# BLDC-PWR-CONROLLER.net
KiCad netlist of a schematic drawn in Altium Designer
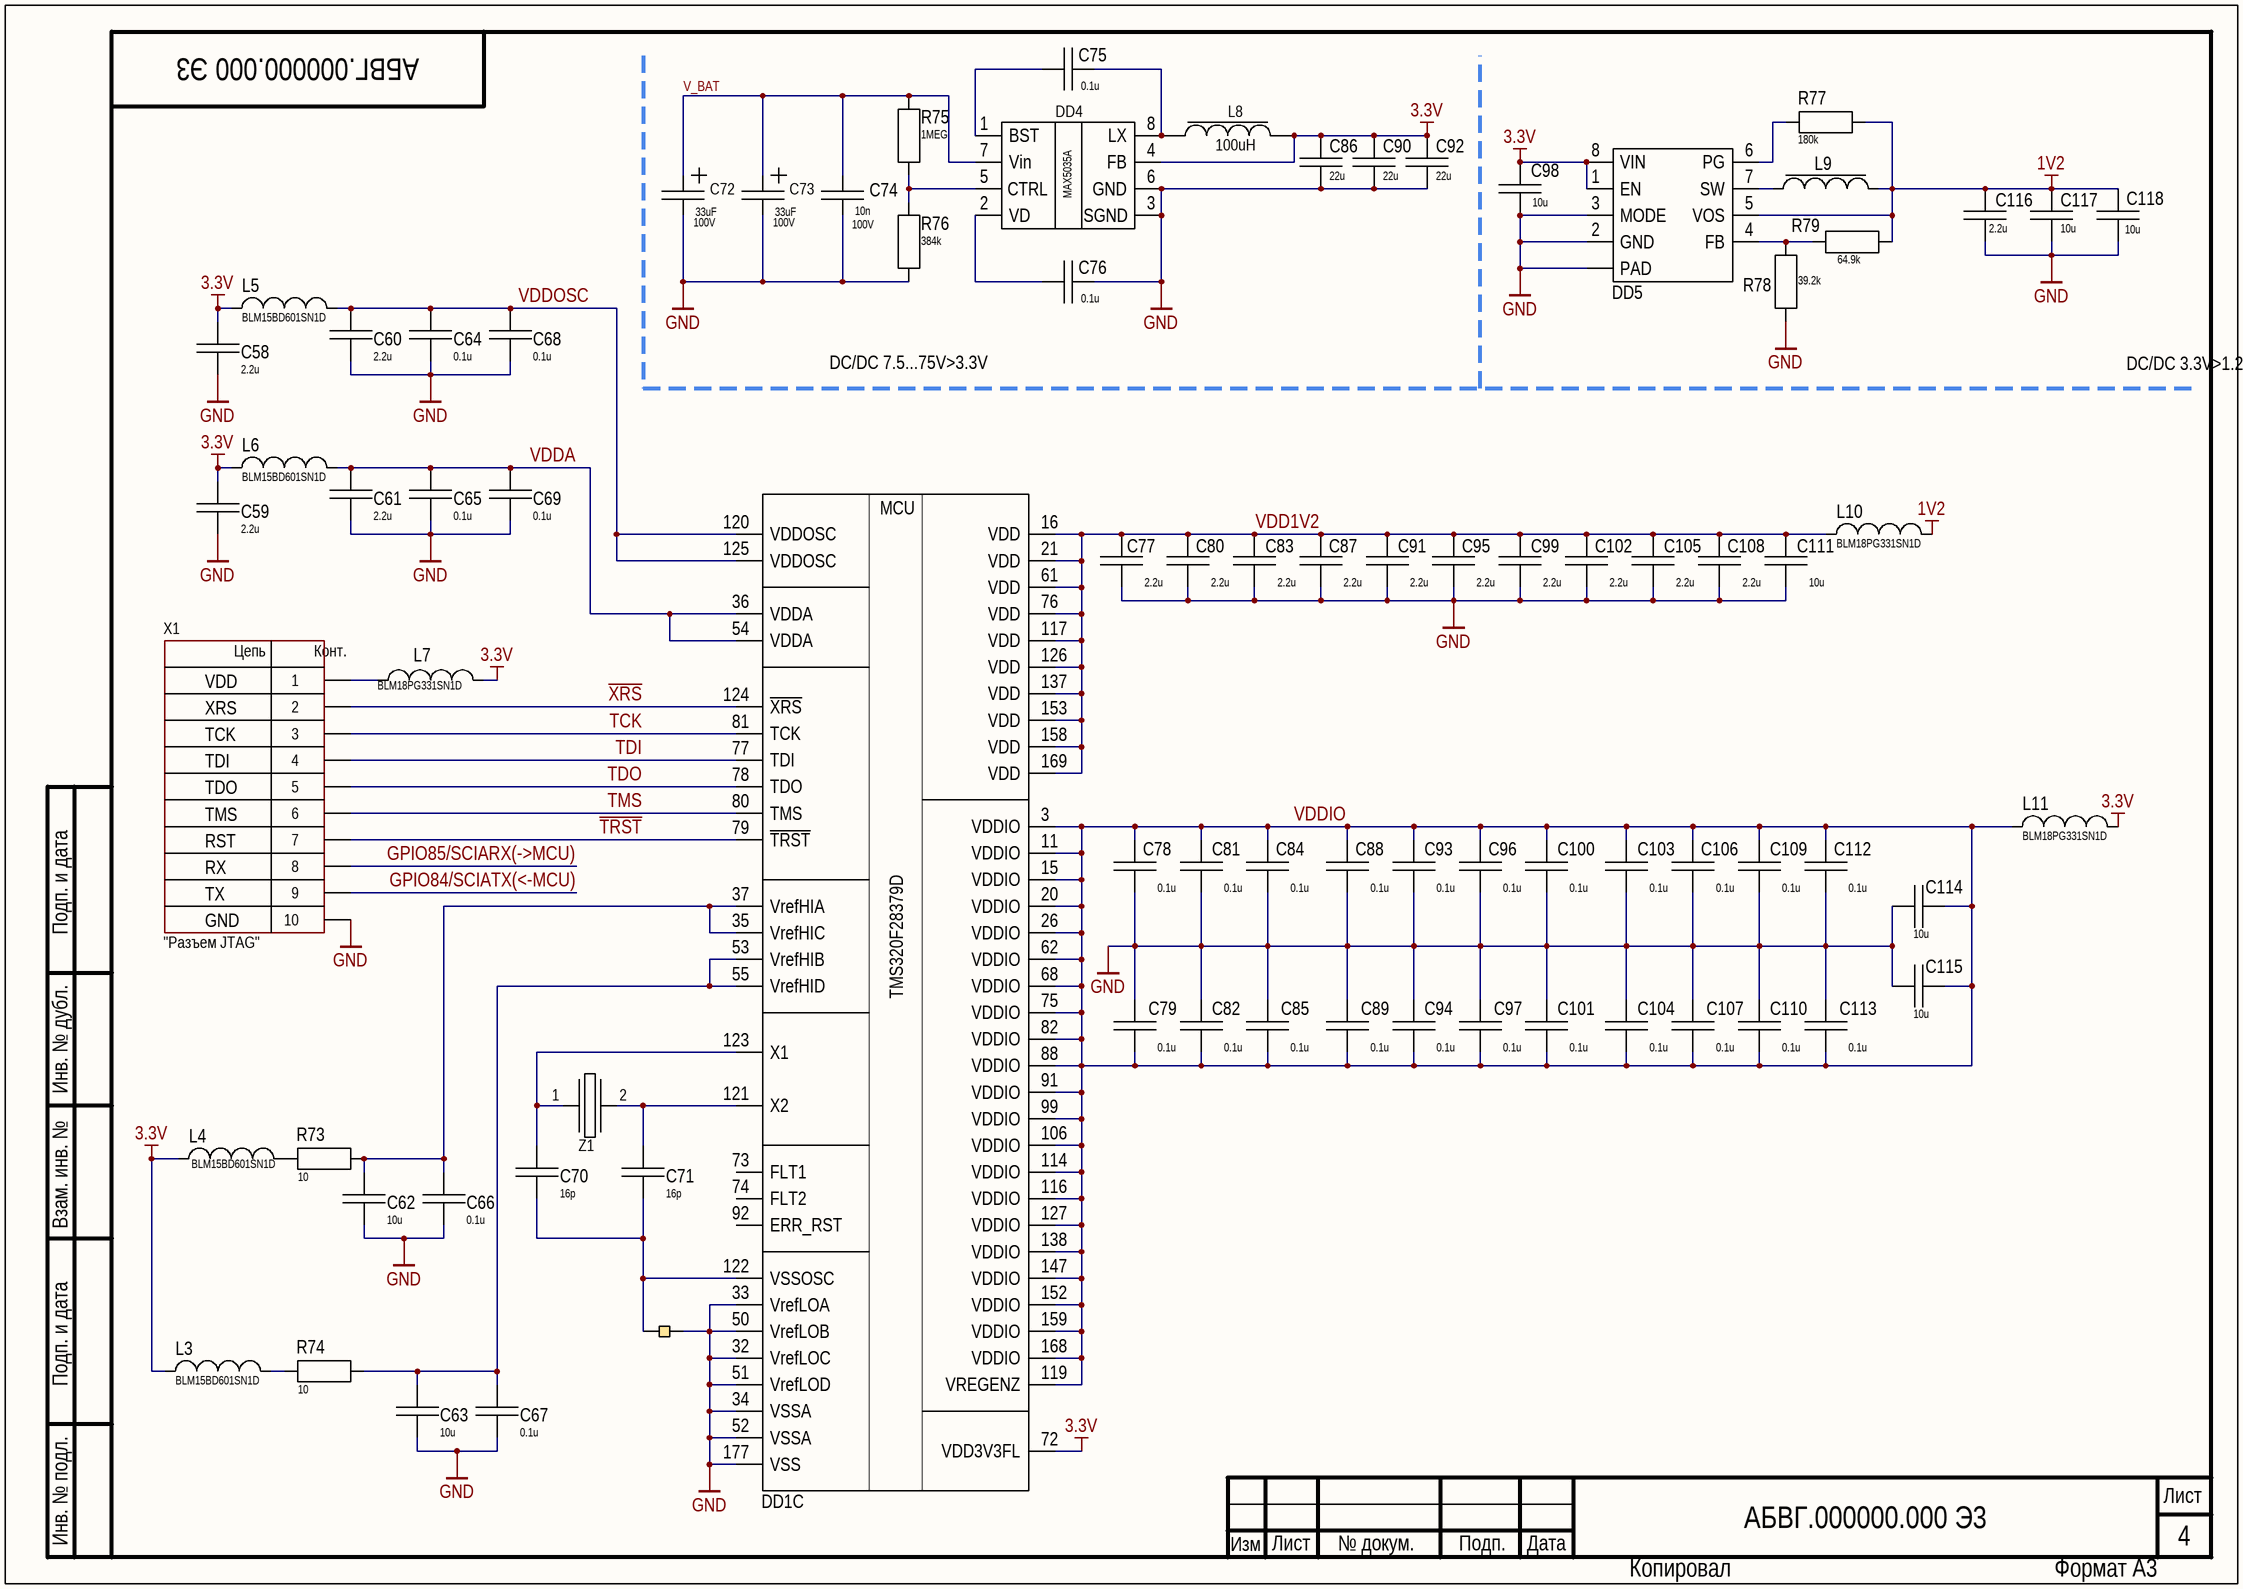
[diagram p0: BLDC-PWR-CONROLLER.SchDoc]

(export (version "E")
  (design (tool "Eeschema 10.0.6"))
  (components
    (comp (ref "C58")
      (value "2.2u")
      (footprint "CAP: 0402")
      (fields (field (name "VOLTAGE") "6.3V") (field (name "PARTNUMBER") "CC0402MRX5R5BB106"))
      (libsource (lib "Fider_Board_Lib") (part "CAP 0402"))
    )
    (comp (ref "C59")
      (value "2.2u")
      (footprint "CAP: 0402")
      (fields (field (name "VOLTAGE") "6.3V") (field (name "PARTNUMBER") "CC0402MRX5R5BB106"))
      (libsource (lib "Fider_Board_Lib") (part "CAP 0402"))
    )
    (comp (ref "C60")
      (value "2.2u")
      (footprint "CAP: 0402")
      (fields (field (name "VOLTAGE") "6.3V") (field (name "PARTNUMBER") "CC0402MRX5R5BB106"))
      (libsource (lib "Fider_Board_Lib") (part "CAP 0402"))
    )
    (comp (ref "C61")
      (value "2.2u")
      (footprint "CAP: 0402")
      (fields (field (name "VOLTAGE") "6.3V") (field (name "PARTNUMBER") "CC0402MRX5R5BB106"))
      (libsource (lib "Fider_Board_Lib") (part "CAP 0402"))
    )
    (comp (ref "C62")
      (value "10u")
      (footprint "CAP: 0402")
      (fields (field (name "VOLTAGE") "6.3V") (field (name "PARTNUMBER") "CC0402MRX5R5BB106"))
      (libsource (lib "Fider_Board_Lib") (part "CAP 0402"))
    )
    (comp (ref "C63")
      (value "10u")
      (footprint "CAP: 0402")
      (fields (field (name "VOLTAGE") "6.3V") (field (name "PARTNUMBER") "CC0402MRX5R5BB106"))
      (libsource (lib "Fider_Board_Lib") (part "CAP 0402"))
    )
    (comp (ref "C64")
      (value "0.1u")
      (footprint "CAP: 0402")
      (fields
        (field (name "VOLTAGE") "10V")
        (field (name "PARTNUMBER") "C0402C104K8PAC")
        (field (name "MANUFACTURER") "Kemet")
      )
      (libsource (lib "Fider_Board_Lib") (part "CAP 0402"))
    )
    (comp (ref "C65")
      (value "0.1u")
      (footprint "CAP: 0402")
      (fields
        (field (name "VOLTAGE") "10V")
        (field (name "PARTNUMBER") "C0402C104K8PAC")
        (field (name "MANUFACTURER") "Kemet")
      )
      (libsource (lib "Fider_Board_Lib") (part "CAP 0402"))
    )
    (comp (ref "C66")
      (value "0.1u")
      (footprint "CAP: 0402")
      (fields
        (field (name "VOLTAGE") "10V")
        (field (name "PARTNUMBER") "C0402C104K8PAC")
        (field (name "MANUFACTURER") "Kemet")
      )
      (libsource (lib "Fider_Board_Lib") (part "CAP 0402"))
    )
    (comp (ref "C67")
      (value "0.1u")
      (footprint "CAP: 0402")
      (fields
        (field (name "VOLTAGE") "10V")
        (field (name "PARTNUMBER") "C0402C104K8PAC")
        (field (name "MANUFACTURER") "Kemet")
      )
      (libsource (lib "Fider_Board_Lib") (part "CAP 0402"))
    )
    (comp (ref "C68")
      (value "0.1u")
      (footprint "CAP: 0402")
      (fields
        (field (name "VOLTAGE") "10V")
        (field (name "PARTNUMBER") "C0402C104K8PAC")
        (field (name "MANUFACTURER") "Kemet")
      )
      (libsource (lib "Fider_Board_Lib") (part "CAP 0402"))
    )
    (comp (ref "C69")
      (value "0.1u")
      (footprint "CAP: 0402")
      (fields
        (field (name "VOLTAGE") "10V")
        (field (name "PARTNUMBER") "C0402C104K8PAC")
        (field (name "MANUFACTURER") "Kemet")
      )
      (libsource (lib "Fider_Board_Lib") (part "CAP 0402"))
    )
    (comp (ref "C70")
      (value "16p")
      (footprint "CAP: 0402")
      (fields
        (field (name "VOLTAGE") "50V")
        (field (name "PARTNUMBER") "GRM1555C1H160JA01D")
        (field (name "MANUFACTURER") "Kemet")
      )
      (libsource (lib "Fider_Board_Lib") (part "CAP 0402"))
    )
    (comp (ref "C71")
      (value "16p")
      (footprint "CAP: 0402")
      (fields
        (field (name "VOLTAGE") "50V")
        (field (name "PARTNUMBER") "GRM1555C1H160JA01D")
        (field (name "MANUFACTURER") "Kemet")
      )
      (libsource (lib "Fider_Board_Lib") (part "CAP 0402"))
    )
    (comp (ref "C72")
      (value "33uF")
      (footprint "ECR08")
      (description "ECR0812")
      (fields (field (name "PARTNUMBER") "JRB2A330M03500800120000B") (field (name "VOLTAGE") "100V"))
      (libsource (lib "capacitors") (part "ECR0812"))
    )
    (comp (ref "C73")
      (value "33uF")
      (footprint "ECR08")
      (description "ECR0812")
      (fields (field (name "PARTNUMBER") "JRB2A330M03500800120000B") (field (name "VOLTAGE") "100V"))
      (libsource (lib "capacitors") (part "ECR0812"))
    )
    (comp (ref "C74")
      (value "10n")
      (footprint "StandardCase:CAP: 0603")
      (fields
        (field (name "MANUFACTURER") "murata")
        (field (name "PARTNUMBER") "GRM188R72A103KA01D")
        (field (name "VALUEMANUFACTURERPARTNUMBER") "Ceramic capacitor, 10n, X7R, ±10%, 100V, 0603, -55...+125°C")
        (field (name "VOLTAGE") "100V")
      )
      (libsource (lib "Capacitor") (part "Ceramic_0603"))
    )
    (comp (ref "C75")
      (value "0.1u")
      (footprint "CAP: 0402")
      (fields
        (field (name "VOLTAGE") "100V")
        (field (name "MANUFACTURER") "Kemet")
        (field (name "TOLERANCE") "10%")
      )
      (libsource (lib "Fider_Board_Lib") (part "CAP 0402"))
    )
    (comp (ref "C76")
      (value "0.1u")
      (footprint "CAP: 0402")
      (fields
        (field (name "VOLTAGE") "100V")
        (field (name "MANUFACTURER") "Kemet")
        (field (name "TOLERANCE") "10%")
      )
      (libsource (lib "Fider_Board_Lib") (part "CAP 0402"))
    )
    (comp (ref "C77")
      (value "2.2u")
      (footprint "CAP: 0402")
      (fields (field (name "VOLTAGE") "6.3V") (field (name "PARTNUMBER") "CC0402MRX5R5BB106"))
      (libsource (lib "Fider_Board_Lib") (part "CAP 0402"))
    )
    (comp (ref "C78")
      (value "0.1u")
      (footprint "CAP: 0402")
      (fields
        (field (name "VOLTAGE") "10V")
        (field (name "PARTNUMBER") "C0402C104K8PAC")
        (field (name "MANUFACTURER") "Kemet")
      )
      (libsource (lib "Fider_Board_Lib") (part "CAP 0402"))
    )
    (comp (ref "C79")
      (value "0.1u")
      (footprint "CAP: 0402")
      (fields
        (field (name "VOLTAGE") "10V")
        (field (name "PARTNUMBER") "C0402C104K8PAC")
        (field (name "MANUFACTURER") "Kemet")
      )
      (libsource (lib "Fider_Board_Lib") (part "CAP 0402"))
    )
    (comp (ref "C80")
      (value "2.2u")
      (footprint "CAP: 0402")
      (fields (field (name "VOLTAGE") "6.3V") (field (name "PARTNUMBER") "CC0402MRX5R5BB106"))
      (libsource (lib "Fider_Board_Lib") (part "CAP 0402"))
    )
    (comp (ref "C81")
      (value "0.1u")
      (footprint "CAP: 0402")
      (fields
        (field (name "VOLTAGE") "10V")
        (field (name "PARTNUMBER") "C0402C104K8PAC")
        (field (name "MANUFACTURER") "Kemet")
      )
      (libsource (lib "Fider_Board_Lib") (part "CAP 0402"))
    )
    (comp (ref "C82")
      (value "0.1u")
      (footprint "CAP: 0402")
      (fields
        (field (name "VOLTAGE") "10V")
        (field (name "PARTNUMBER") "C0402C104K8PAC")
        (field (name "MANUFACTURER") "Kemet")
      )
      (libsource (lib "Fider_Board_Lib") (part "CAP 0402"))
    )
    (comp (ref "C83")
      (value "2.2u")
      (footprint "CAP: 0402")
      (fields (field (name "VOLTAGE") "6.3V") (field (name "PARTNUMBER") "CC0402MRX5R5BB106"))
      (libsource (lib "Fider_Board_Lib") (part "CAP 0402"))
    )
    (comp (ref "C84")
      (value "0.1u")
      (footprint "CAP: 0402")
      (fields
        (field (name "VOLTAGE") "10V")
        (field (name "PARTNUMBER") "C0402C104K8PAC")
        (field (name "MANUFACTURER") "Kemet")
      )
      (libsource (lib "Fider_Board_Lib") (part "CAP 0402"))
    )
    (comp (ref "C85")
      (value "0.1u")
      (footprint "CAP: 0402")
      (fields
        (field (name "VOLTAGE") "10V")
        (field (name "PARTNUMBER") "C0402C104K8PAC")
        (field (name "MANUFACTURER") "Kemet")
      )
      (libsource (lib "Fider_Board_Lib") (part "CAP 0402"))
    )
    (comp (ref "C86")
      (value "22u")
      (footprint "CAP: 0805")
      (fields (field (name "VOLTAGE") "6.3V") (field (name "PARTNUMBER") "GRM21BR60J226M*"))
      (libsource (lib "Fider_Board_Lib") (part "CAP 0805"))
    )
    (comp (ref "C87")
      (value "2.2u")
      (footprint "CAP: 0402")
      (fields (field (name "VOLTAGE") "6.3V") (field (name "PARTNUMBER") "CC0402MRX5R5BB106"))
      (libsource (lib "Fider_Board_Lib") (part "CAP 0402"))
    )
    (comp (ref "C88")
      (value "0.1u")
      (footprint "CAP: 0402")
      (fields
        (field (name "VOLTAGE") "10V")
        (field (name "PARTNUMBER") "C0402C104K8PAC")
        (field (name "MANUFACTURER") "Kemet")
      )
      (libsource (lib "Fider_Board_Lib") (part "CAP 0402"))
    )
    (comp (ref "C89")
      (value "0.1u")
      (footprint "CAP: 0402")
      (fields
        (field (name "VOLTAGE") "10V")
        (field (name "PARTNUMBER") "C0402C104K8PAC")
        (field (name "MANUFACTURER") "Kemet")
      )
      (libsource (lib "Fider_Board_Lib") (part "CAP 0402"))
    )
    (comp (ref "C90")
      (value "22u")
      (footprint "CAP: 0805")
      (fields (field (name "VOLTAGE") "6.3V") (field (name "PARTNUMBER") "GRM21BR60J226M*"))
      (libsource (lib "Fider_Board_Lib") (part "CAP 0805"))
    )
    (comp (ref "C91")
      (value "2.2u")
      (footprint "CAP: 0402")
      (fields (field (name "VOLTAGE") "6.3V") (field (name "PARTNUMBER") "CC0402MRX5R5BB106"))
      (libsource (lib "Fider_Board_Lib") (part "CAP 0402"))
    )
    (comp (ref "C92")
      (value "22u")
      (footprint "CAP: 0805")
      (fields (field (name "VOLTAGE") "6.3V") (field (name "PARTNUMBER") "GRM21BR60J226M*"))
      (libsource (lib "Fider_Board_Lib") (part "CAP 0805"))
    )
    (comp (ref "C93")
      (value "0.1u")
      (footprint "CAP: 0402")
      (fields
        (field (name "VOLTAGE") "10V")
        (field (name "PARTNUMBER") "C0402C104K8PAC")
        (field (name "MANUFACTURER") "Kemet")
      )
      (libsource (lib "Fider_Board_Lib") (part "CAP 0402"))
    )
    (comp (ref "C94")
      (value "0.1u")
      (footprint "CAP: 0402")
      (fields
        (field (name "VOLTAGE") "10V")
        (field (name "PARTNUMBER") "C0402C104K8PAC")
        (field (name "MANUFACTURER") "Kemet")
      )
      (libsource (lib "Fider_Board_Lib") (part "CAP 0402"))
    )
    (comp (ref "C95")
      (value "2.2u")
      (footprint "CAP: 0402")
      (fields (field (name "VOLTAGE") "6.3V") (field (name "PARTNUMBER") "CC0402MRX5R5BB106"))
      (libsource (lib "Fider_Board_Lib") (part "CAP 0402"))
    )
    (comp (ref "C96")
      (value "0.1u")
      (footprint "CAP: 0402")
      (fields
        (field (name "VOLTAGE") "10V")
        (field (name "PARTNUMBER") "C0402C104K8PAC")
        (field (name "MANUFACTURER") "Kemet")
      )
      (libsource (lib "Fider_Board_Lib") (part "CAP 0402"))
    )
    (comp (ref "C97")
      (value "0.1u")
      (footprint "CAP: 0402")
      (fields
        (field (name "VOLTAGE") "10V")
        (field (name "PARTNUMBER") "C0402C104K8PAC")
        (field (name "MANUFACTURER") "Kemet")
      )
      (libsource (lib "Fider_Board_Lib") (part "CAP 0402"))
    )
    (comp (ref "C98")
      (value "10u")
      (footprint "CAP: 0805")
      (fields (field (name "VOLTAGE") "6.3V") (field (name "PARTNUMBER") "CC0402MRX5R5BB106"))
      (libsource (lib "Fider_Board_Lib") (part "CAP 0805"))
    )
    (comp (ref "C99")
      (value "2.2u")
      (footprint "CAP: 0402")
      (fields (field (name "VOLTAGE") "6.3V") (field (name "PARTNUMBER") "CC0402MRX5R5BB106"))
      (libsource (lib "Fider_Board_Lib") (part "CAP 0402"))
    )
    (comp (ref "C100")
      (value "0.1u")
      (footprint "CAP: 0402")
      (fields
        (field (name "VOLTAGE") "10V")
        (field (name "PARTNUMBER") "C0402C104K8PAC")
        (field (name "MANUFACTURER") "Kemet")
      )
      (libsource (lib "Fider_Board_Lib") (part "CAP 0402"))
    )
    (comp (ref "C101")
      (value "0.1u")
      (footprint "CAP: 0402")
      (fields
        (field (name "VOLTAGE") "10V")
        (field (name "PARTNUMBER") "C0402C104K8PAC")
        (field (name "MANUFACTURER") "Kemet")
      )
      (libsource (lib "Fider_Board_Lib") (part "CAP 0402"))
    )
    (comp (ref "C102")
      (value "2.2u")
      (footprint "CAP: 0402")
      (fields (field (name "VOLTAGE") "6.3V") (field (name "PARTNUMBER") "CC0402MRX5R5BB106"))
      (libsource (lib "Fider_Board_Lib") (part "CAP 0402"))
    )
    (comp (ref "C103")
      (value "0.1u")
      (footprint "CAP: 0402")
      (fields
        (field (name "VOLTAGE") "10V")
        (field (name "PARTNUMBER") "C0402C104K8PAC")
        (field (name "MANUFACTURER") "Kemet")
      )
      (libsource (lib "Fider_Board_Lib") (part "CAP 0402"))
    )
    (comp (ref "C104")
      (value "0.1u")
      (footprint "CAP: 0402")
      (fields
        (field (name "VOLTAGE") "10V")
        (field (name "PARTNUMBER") "C0402C104K8PAC")
        (field (name "MANUFACTURER") "Kemet")
      )
      (libsource (lib "Fider_Board_Lib") (part "CAP 0402"))
    )
    (comp (ref "C105")
      (value "2.2u")
      (footprint "CAP: 0402")
      (fields (field (name "VOLTAGE") "6.3V") (field (name "PARTNUMBER") "CC0402MRX5R5BB106"))
      (libsource (lib "Fider_Board_Lib") (part "CAP 0402"))
    )
    (comp (ref "C106")
      (value "0.1u")
      (footprint "CAP: 0402")
      (fields
        (field (name "VOLTAGE") "10V")
        (field (name "PARTNUMBER") "C0402C104K8PAC")
        (field (name "MANUFACTURER") "Kemet")
      )
      (libsource (lib "Fider_Board_Lib") (part "CAP 0402"))
    )
    (comp (ref "C107")
      (value "0.1u")
      (footprint "CAP: 0402")
      (fields
        (field (name "VOLTAGE") "10V")
        (field (name "PARTNUMBER") "C0402C104K8PAC")
        (field (name "MANUFACTURER") "Kemet")
      )
      (libsource (lib "Fider_Board_Lib") (part "CAP 0402"))
    )
    (comp (ref "C108")
      (value "2.2u")
      (footprint "CAP: 0402")
      (fields (field (name "VOLTAGE") "6.3V") (field (name "PARTNUMBER") "CC0402MRX5R5BB106"))
      (libsource (lib "Fider_Board_Lib") (part "CAP 0402"))
    )
    (comp (ref "C109")
      (value "0.1u")
      (footprint "CAP: 0402")
      (fields
        (field (name "VOLTAGE") "10V")
        (field (name "PARTNUMBER") "C0402C104K8PAC")
        (field (name "MANUFACTURER") "Kemet")
      )
      (libsource (lib "Fider_Board_Lib") (part "CAP 0402"))
    )
    (comp (ref "C110")
      (value "0.1u")
      (footprint "CAP: 0402")
      (fields
        (field (name "VOLTAGE") "10V")
        (field (name "PARTNUMBER") "C0402C104K8PAC")
        (field (name "MANUFACTURER") "Kemet")
      )
      (libsource (lib "Fider_Board_Lib") (part "CAP 0402"))
    )
    (comp (ref "C111")
      (value "10u")
      (footprint "CAP: 0402")
      (fields (field (name "VOLTAGE") "6.3V") (field (name "PARTNUMBER") "CC0402MRX5R5BB106"))
      (libsource (lib "Fider_Board_Lib") (part "CAP 0402"))
    )
    (comp (ref "C112")
      (value "0.1u")
      (footprint "CAP: 0402")
      (fields
        (field (name "VOLTAGE") "10V")
        (field (name "PARTNUMBER") "C0402C104K8PAC")
        (field (name "MANUFACTURER") "Kemet")
      )
      (libsource (lib "Fider_Board_Lib") (part "CAP 0402"))
    )
    (comp (ref "C113")
      (value "0.1u")
      (footprint "CAP: 0402")
      (fields
        (field (name "VOLTAGE") "10V")
        (field (name "PARTNUMBER") "C0402C104K8PAC")
        (field (name "MANUFACTURER") "Kemet")
      )
      (libsource (lib "Fider_Board_Lib") (part "CAP 0402"))
    )
    (comp (ref "C114")
      (value "10u")
      (footprint "CAP: 0402")
      (fields (field (name "VOLTAGE") "6.3V") (field (name "PARTNUMBER") "CC0402MRX5R5BB106"))
      (libsource (lib "Fider_Board_Lib") (part "CAP 0402"))
    )
    (comp (ref "C115")
      (value "10u")
      (footprint "CAP: 0402")
      (fields (field (name "VOLTAGE") "6.3V") (field (name "PARTNUMBER") "CC0402MRX5R5BB106"))
      (libsource (lib "Fider_Board_Lib") (part "CAP 0402"))
    )
    (comp (ref "C116")
      (value "2.2u")
      (footprint "CAP: 0402")
      (fields (field (name "VOLTAGE") "6.3V") (field (name "PARTNUMBER") "CC0402MRX5R5BB106"))
      (libsource (lib "Fider_Board_Lib") (part "CAP 0402"))
    )
    (comp (ref "C117")
      (value "10u")
      (footprint "CAP: 0805")
      (fields (field (name "VOLTAGE") "6.3V") (field (name "PARTNUMBER") "CC0402MRX5R5BB106"))
      (libsource (lib "Fider_Board_Lib") (part "CAP 0805"))
    )
    (comp (ref "C118")
      (value "10u")
      (footprint "CAP: 0805")
      (fields (field (name "VOLTAGE") "6.3V") (field (name "PARTNUMBER") "CC0402MRX5R5BB106"))
      (libsource (lib "Fider_Board_Lib") (part "CAP 0805"))
    )
    (comp (ref "DD1")
      (value "TMS320F28379DPTP_LACID")
      (footprint "176-HLQFP")
      (fields (field (name "PARTNUMBER") "TMS320F28379DPTPT"))
      (libsource (lib "BKM_SCH_Lib") (part "TMS320F28379DPTP_LACID"))
    )
    (comp (ref "DD4")
      (value "MAX5035A")
      (footprint "SOIC-8-150-1.27")
      (libsource (lib "BKM_SCH_Lib") (part "MAX5035*"))
    )
    (comp (ref "DD5")
      (value "TPS62080ADSGT")
      (footprint "8-WSON 2.1x2.1")
      (fields (field (name "PARTNUMBER") "TPS61023DRLR"))
      (libsource (lib "BKM_SCH_Lib") (part "TPS62080ADSGT"))
    )
    (comp (ref "L3")
      (value "BLM15BD601SN1D")
      (footprint "IND: 0402")
      (libsource (lib "Fider_Board_Lib") (part "BLM15BD601SN1D"))
    )
    (comp (ref "L4")
      (value "BLM15BD601SN1D")
      (footprint "IND: 0402")
      (libsource (lib "Fider_Board_Lib") (part "BLM15BD601SN1D"))
    )
    (comp (ref "L5")
      (value "BLM15BD601SN1D")
      (footprint "IND: 0402")
      (libsource (lib "Fider_Board_Lib") (part "BLM15BD601SN1D"))
    )
    (comp (ref "L6")
      (value "BLM15BD601SN1D")
      (footprint "IND: 0402")
      (libsource (lib "Fider_Board_Lib") (part "BLM15BD601SN1D"))
    )
    (comp (ref "L7")
      (value "BLM18PG331SN1D")
      (footprint "IND: 0603")
      (libsource (lib "") (part "BLM18PG331SN1D_1"))
    )
    (comp (ref "L8")
      (value "100uH")
      (footprint "CustomCase:IND: SRR1208")
      (fields
        (field (name "MANUFACTURER") "EPCOS")
        (field (name "PARTNUMBER") "B82477G4104M000")
        (field (name "TOLERANCE") "20%")
      )
      (libsource (lib "Inductor") (part "Inductor_SRR1208"))
    )
    (comp (ref "L9")
      (value "LQH3NPN")
      (footprint "IND: LQH3NP")
      (fields (field (name "PARTNUMBER") "LQH3NPN1R0NJ0L"))
      (libsource (lib "BKM_SCH_Lib") (part "LQH3NPN"))
    )
    (comp (ref "L10")
      (value "BLM18PG331SN1D")
      (footprint "IND: 0603")
      (libsource (lib "Fider_Board_Lib") (part "BLM18PG331SN1D"))
    )
    (comp (ref "L11")
      (value "BLM18PG331SN1D")
      (footprint "IND: 0603")
      (libsource (lib "Fider_Board_Lib") (part "BLM18PG331SN1D"))
    )
    (comp (ref "NT19") (value "~") (footprint "CON: NT") (libsource (lib "BKM_SCH_Lib") (part "NT")))
    (comp (ref "R73")
      (value "10")
      (footprint "RES: 0402")
      (fields (field (name "PARTNUMBER") "RC0402FR-071KL") (field (name "TOLERANCE") "1%"))
      (libsource (lib "Fider_Board_Lib") (part "RES 0402"))
    )
    (comp (ref "R74")
      (value "10")
      (footprint "RES: 0402")
      (fields (field (name "PARTNUMBER") "RC0402FR-071KL") (field (name "TOLERANCE") "1%"))
      (libsource (lib "Fider_Board_Lib") (part "RES 0402"))
    )
    (comp (ref "R75")
      (value "1MEG")
      (footprint "RES: 0402")
      (fields (field (name "PARTNUMBER") "RC0402FR-1339K2L") (field (name "TOLERANCE") "1%"))
      (libsource (lib "Fider_Board_Lib") (part "RES 0402"))
    )
    (comp (ref "R76")
      (value "384k")
      (footprint "RES: 0402")
      (fields (field (name "PARTNUMBER") "RC0402FR-1339K2L") (field (name "TOLERANCE") "1%"))
      (libsource (lib "Fider_Board_Lib") (part "RES 0402"))
    )
    (comp (ref "R77")
      (value "180k")
      (footprint "RES: 0402")
      (fields (field (name "PARTNUMBER") "RC0402FR-07180RL") (field (name "TOLERANCE") "1%"))
      (libsource (lib "Fider_Board_Lib") (part "RES 0402"))
    )
    (comp (ref "R78")
      (value "39.2k")
      (footprint "RES: 0402")
      (fields (field (name "PARTNUMBER") "RC0402FR-1339K2L") (field (name "TOLERANCE") "1%"))
      (libsource (lib "Fider_Board_Lib") (part "RES 0402"))
    )
    (comp (ref "R79")
      (value "64.9k")
      (footprint "RES: 0402")
      (fields (field (name "PARTNUMBER") "RC0402FR-1364K9L") (field (name "TOLERANCE") "1%"))
      (libsource (lib "Fider_Board_Lib") (part "RES 0402"))
    )
    (comp (ref "X1")
      (value "~")
      (footprint "CustomCase:CON: PLD-10")
      (fields
        (field (name "MANUFACTURER") "Connfly")
        (field (name "VALUEMANUFACTURERPARTNUMBER") "Connector, 10pin, 2.54mm, 500VAC, 3A")
        (field (name "PARTNUMBER") "PLD-10")
        (field (name "COMMENTTEXT") "\"Разъем JTAG\"")
      )
      (libsource (lib "Connector") (part "PLD-10"))
    )
    (comp (ref "Z1")
      (value "~")
      (footprint "CustomCase:OSC: HC49SM")
      (fields
        (field (name "MANUFACTURER") "Epson")
        (field (name "PARTNUMBER") "FC-135 32.7680KA-A5")
        (field (name "VALUEMANUFACTURERPARTNUMBER") "Crystal, , 12.5pF, ±20ppm, case 3215, -40...+85°C")
      )
      (libsource (lib "Oscilator") (part "Crystal_HC-49SM"))
    )
  )
  (nets
    (net (code "1") (name "/GPIO84{slash}SCIATX(<-MCU)") (class "Default")
      (node (ref "X1") (pin "9") (pinfunction "9_9") (pintype "power_in"))
    )
    (net (code "2") (name "/GPIO85{slash}SCIARX(->MCU)") (class "Default")
      (node (ref "X1") (pin "8") (pinfunction "8_8") (pintype "power_in"))
    )
    (net (code "3") (name "/TCK") (class "Default")
      (node (ref "DD1") (pin "81") (pinfunction "TCK_81") (pintype "power_in"))
      (node (ref "X1") (pin "3") (pinfunction "3_3") (pintype "power_in"))
    )
    (net (code "4") (name "/TDI") (class "Default")
      (node (ref "DD1") (pin "77") (pinfunction "TDI_77") (pintype "power_in"))
      (node (ref "X1") (pin "4") (pinfunction "4_4") (pintype "power_in"))
    )
    (net (code "5") (name "/TDO") (class "Default")
      (node (ref "DD1") (pin "78") (pinfunction "TDO_78") (pintype "power_in"))
      (node (ref "X1") (pin "5") (pinfunction "5_5") (pintype "power_in"))
    )
    (net (code "6") (name "/TMS") (class "Default")
      (node (ref "DD1") (pin "80") (pinfunction "TMS_80") (pintype "power_in"))
      (node (ref "X1") (pin "6") (pinfunction "6_6") (pintype "power_in"))
    )
    (net (code "7") (name "/VDD1V2") (class "Default")
      (node (ref "C102") (pin "2") (pinfunction "2_2") (pintype "passive"))
      (node (ref "C105") (pin "2") (pinfunction "2_2") (pintype "passive"))
      (node (ref "C108") (pin "2") (pinfunction "2_2") (pintype "passive"))
      (node (ref "C111") (pin "2") (pinfunction "2_2") (pintype "passive"))
      (node (ref "C77") (pin "2") (pinfunction "2_2") (pintype "passive"))
      (node (ref "C80") (pin "2") (pinfunction "2_2") (pintype "passive"))
      (node (ref "C83") (pin "2") (pinfunction "2_2") (pintype "passive"))
      (node (ref "C87") (pin "2") (pinfunction "2_2") (pintype "passive"))
      (node (ref "C91") (pin "2") (pinfunction "2_2") (pintype "passive"))
      (node (ref "C95") (pin "2") (pinfunction "2_2") (pintype "passive"))
      (node (ref "C99") (pin "2") (pinfunction "2_2") (pintype "passive"))
      (node (ref "DD1") (pin "117") (pinfunction "VDD_117") (pintype "power_in"))
      (node (ref "DD1") (pin "126") (pinfunction "VDD_126") (pintype "power_in"))
      (node (ref "DD1") (pin "137") (pinfunction "VDD_137") (pintype "power_in"))
      (node (ref "DD1") (pin "153") (pinfunction "VDD_153") (pintype "power_in"))
      (node (ref "DD1") (pin "158") (pinfunction "VDD_158") (pintype "power_in"))
      (node (ref "DD1") (pin "16") (pinfunction "VDD_16") (pintype "power_in"))
      (node (ref "DD1") (pin "169") (pinfunction "VDD_169") (pintype "power_in"))
      (node (ref "DD1") (pin "21") (pinfunction "VDD_21") (pintype "power_in"))
      (node (ref "DD1") (pin "61") (pinfunction "VDD_61") (pintype "power_in"))
      (node (ref "DD1") (pin "76") (pinfunction "VDD_76") (pintype "power_in"))
      (node (ref "L10") (pin "1") (pinfunction "1_1") (pintype "passive"))
    )
    (net (code "8") (name "/VDDA") (class "Default")
      (node (ref "C61") (pin "2") (pinfunction "2_2") (pintype "passive"))
      (node (ref "C65") (pin "2") (pinfunction "2_2") (pintype "passive"))
      (node (ref "C69") (pin "2") (pinfunction "2_2") (pintype "passive"))
      (node (ref "DD1") (pin "36") (pinfunction "VDDA_36") (pintype "power_in"))
      (node (ref "DD1") (pin "54") (pinfunction "VDDA_54") (pintype "power_in"))
      (node (ref "L6") (pin "2") (pinfunction "2_2") (pintype "passive"))
    )
    (net (code "9") (name "/VDDIO") (class "Default")
      (node (ref "C100") (pin "2") (pinfunction "2_2") (pintype "passive"))
      (node (ref "C101") (pin "1") (pinfunction "1_1") (pintype "passive"))
      (node (ref "C103") (pin "2") (pinfunction "2_2") (pintype "passive"))
      (node (ref "C104") (pin "1") (pinfunction "1_1") (pintype "passive"))
      (node (ref "C106") (pin "2") (pinfunction "2_2") (pintype "passive"))
      (node (ref "C107") (pin "1") (pinfunction "1_1") (pintype "passive"))
      (node (ref "C109") (pin "2") (pinfunction "2_2") (pintype "passive"))
      (node (ref "C110") (pin "1") (pinfunction "1_1") (pintype "passive"))
      (node (ref "C112") (pin "2") (pinfunction "2_2") (pintype "passive"))
      (node (ref "C113") (pin "1") (pinfunction "1_1") (pintype "passive"))
      (node (ref "C114") (pin "1") (pinfunction "1_1") (pintype "passive"))
      (node (ref "C115") (pin "1") (pinfunction "1_1") (pintype "passive"))
      (node (ref "C78") (pin "2") (pinfunction "2_2") (pintype "passive"))
      (node (ref "C79") (pin "1") (pinfunction "1_1") (pintype "passive"))
      (node (ref "C81") (pin "2") (pinfunction "2_2") (pintype "passive"))
      (node (ref "C82") (pin "1") (pinfunction "1_1") (pintype "passive"))
      (node (ref "C84") (pin "2") (pinfunction "2_2") (pintype "passive"))
      (node (ref "C85") (pin "1") (pinfunction "1_1") (pintype "passive"))
      (node (ref "C88") (pin "2") (pinfunction "2_2") (pintype "passive"))
      (node (ref "C89") (pin "1") (pinfunction "1_1") (pintype "passive"))
      (node (ref "C93") (pin "2") (pinfunction "2_2") (pintype "passive"))
      (node (ref "C94") (pin "1") (pinfunction "1_1") (pintype "passive"))
      (node (ref "C96") (pin "2") (pinfunction "2_2") (pintype "passive"))
      (node (ref "C97") (pin "1") (pinfunction "1_1") (pintype "passive"))
      (node (ref "DD1") (pin "106") (pinfunction "VDDIO_106") (pintype "power_in"))
      (node (ref "DD1") (pin "11") (pinfunction "VDDIO_11") (pintype "power_in"))
      (node (ref "DD1") (pin "114") (pinfunction "VDDIO_114") (pintype "power_in"))
      (node (ref "DD1") (pin "116") (pinfunction "VDDIO_116") (pintype "power_in"))
      (node (ref "DD1") (pin "119") (pinfunction "VREGENZ_119") (pintype "power_in"))
      (node (ref "DD1") (pin "127") (pinfunction "VDDIO_127") (pintype "power_in"))
      (node (ref "DD1") (pin "138") (pinfunction "VDDIO_138") (pintype "power_in"))
      (node (ref "DD1") (pin "147") (pinfunction "VDDIO_147") (pintype "power_in"))
      (node (ref "DD1") (pin "15") (pinfunction "VDDIO_15") (pintype "power_in"))
      (node (ref "DD1") (pin "152") (pinfunction "VDDIO_152") (pintype "power_in"))
      (node (ref "DD1") (pin "159") (pinfunction "VDDIO_159") (pintype "power_in"))
      (node (ref "DD1") (pin "168") (pinfunction "VDDIO_168") (pintype "power_in"))
      (node (ref "DD1") (pin "20") (pinfunction "VDDIO_20") (pintype "power_in"))
      (node (ref "DD1") (pin "26") (pinfunction "VDDIO_26") (pintype "power_in"))
      (node (ref "DD1") (pin "3") (pinfunction "VDDIO_3") (pintype "power_in"))
      (node (ref "DD1") (pin "62") (pinfunction "VDDIO_62") (pintype "power_in"))
      (node (ref "DD1") (pin "68") (pinfunction "VDDIO_68") (pintype "power_in"))
      (node (ref "DD1") (pin "75") (pinfunction "VDDIO_75") (pintype "power_in"))
      (node (ref "DD1") (pin "82") (pinfunction "VDDIO_82") (pintype "power_in"))
      (node (ref "DD1") (pin "88") (pinfunction "VDDIO_88") (pintype "power_in"))
      (node (ref "DD1") (pin "91") (pinfunction "VDDIO_91") (pintype "power_in"))
      (node (ref "DD1") (pin "99") (pinfunction "VDDIO_99") (pintype "power_in"))
      (node (ref "L11") (pin "1") (pinfunction "1_1") (pintype "passive"))
    )
    (net (code "10") (name "/VDDOSC") (class "Default")
      (node (ref "C60") (pin "2") (pinfunction "2_2") (pintype "passive"))
      (node (ref "C64") (pin "2") (pinfunction "2_2") (pintype "passive"))
      (node (ref "C68") (pin "2") (pinfunction "2_2") (pintype "passive"))
      (node (ref "DD1") (pin "120") (pinfunction "VDDOSC_120") (pintype "power_in"))
      (node (ref "DD1") (pin "125") (pinfunction "VDDOSC_125") (pintype "power_in"))
      (node (ref "L5") (pin "2") (pinfunction "2_2") (pintype "passive"))
    )
    (net (code "11") (name "/V_BAT") (class "Default")
      (node (ref "C72") (pin "1") (pinfunction "1_1") (pintype "passive"))
      (node (ref "C73") (pin "1") (pinfunction "1_1") (pintype "passive"))
      (node (ref "C74") (pin "2") (pinfunction "2_2") (pintype "power_in"))
      (node (ref "DD4") (pin "7") (pinfunction "Vin_7") (pintype "passive"))
      (node (ref "R75") (pin "2") (pinfunction "2_2") (pintype "passive"))
    )
    (net (code "12") (name "/~{TRST}") (class "Default")
      (node (ref "DD1") (pin "79") (pinfunction "~{TRST}_79") (pintype "power_in"))
      (node (ref "X1") (pin "7") (pinfunction "7_7") (pintype "power_in"))
    )
    (net (code "13") (name "/~{XRS}") (class "Default")
      (node (ref "DD1") (pin "124") (pinfunction "~{XRS}_124") (pintype "power_in"))
      (node (ref "X1") (pin "2") (pinfunction "2_2") (pintype "passive"))
    )
    (net (code "14") (name "1V2") (class "Default")
      (node (ref "C116") (pin "2") (pinfunction "2_2") (pintype "passive"))
      (node (ref "C117") (pin "2") (pinfunction "2_2") (pintype "passive"))
      (node (ref "C118") (pin "2") (pinfunction "2_2") (pintype "passive"))
      (node (ref "DD5") (pin "5") (pinfunction "VOS_5") (pintype "passive"))
      (node (ref "L10") (pin "2") (pinfunction "2_2") (pintype "passive"))
      (node (ref "L9") (pin "1") (pinfunction "1_1") (pintype "passive"))
      (node (ref "R77") (pin "1") (pinfunction "1_1") (pintype "passive"))
      (node (ref "R79") (pin "1") (pinfunction "1_1") (pintype "passive"))
    )
    (net (code "15") (name "3.3V") (class "Default")
      (node (ref "C58") (pin "2") (pinfunction "2_2") (pintype "passive"))
      (node (ref "C59") (pin "2") (pinfunction "2_2") (pintype "passive"))
      (node (ref "C86") (pin "2") (pinfunction "2_2") (pintype "passive"))
      (node (ref "C90") (pin "2") (pinfunction "2_2") (pintype "passive"))
      (node (ref "C92") (pin "2") (pinfunction "2_2") (pintype "passive"))
      (node (ref "C98") (pin "2") (pinfunction "2_2") (pintype "passive"))
      (node (ref "DD1") (pin "72") (pinfunction "VDD3V3FL_72") (pintype "power_in"))
      (node (ref "DD4") (pin "4") (pinfunction "FB_4") (pintype "passive"))
      (node (ref "DD5") (pin "1") (pinfunction "EN_1") (pintype "passive"))
      (node (ref "DD5") (pin "8") (pinfunction "VIN_8") (pintype "passive"))
      (node (ref "L11") (pin "2") (pinfunction "2_2") (pintype "passive"))
      (node (ref "L3") (pin "1") (pinfunction "1_1") (pintype "passive"))
      (node (ref "L4") (pin "1") (pinfunction "1_1") (pintype "passive"))
      (node (ref "L5") (pin "1") (pinfunction "1_1") (pintype "passive"))
      (node (ref "L6") (pin "1") (pinfunction "1_1") (pintype "passive"))
      (node (ref "L7") (pin "1") (pinfunction "1_1") (pintype "passive"))
      (node (ref "L8") (pin "1") (pinfunction "1_1") (pintype "passive"))
    )
    (net (code "16") (name "GND") (class "Default")
      (node (ref "C100") (pin "1") (pinfunction "1_1") (pintype "passive"))
      (node (ref "C101") (pin "2") (pinfunction "2_2") (pintype "passive"))
      (node (ref "C102") (pin "1") (pinfunction "1_1") (pintype "passive"))
      (node (ref "C103") (pin "1") (pinfunction "1_1") (pintype "passive"))
      (node (ref "C104") (pin "2") (pinfunction "2_2") (pintype "passive"))
      (node (ref "C105") (pin "1") (pinfunction "1_1") (pintype "passive"))
      (node (ref "C106") (pin "1") (pinfunction "1_1") (pintype "passive"))
      (node (ref "C107") (pin "2") (pinfunction "2_2") (pintype "passive"))
      (node (ref "C108") (pin "1") (pinfunction "1_1") (pintype "passive"))
      (node (ref "C109") (pin "1") (pinfunction "1_1") (pintype "passive"))
      (node (ref "C110") (pin "2") (pinfunction "2_2") (pintype "passive"))
      (node (ref "C111") (pin "1") (pinfunction "1_1") (pintype "passive"))
      (node (ref "C112") (pin "1") (pinfunction "1_1") (pintype "passive"))
      (node (ref "C113") (pin "2") (pinfunction "2_2") (pintype "passive"))
      (node (ref "C114") (pin "2") (pinfunction "2_2") (pintype "passive"))
      (node (ref "C115") (pin "2") (pinfunction "2_2") (pintype "passive"))
      (node (ref "C116") (pin "1") (pinfunction "1_1") (pintype "passive"))
      (node (ref "C117") (pin "1") (pinfunction "1_1") (pintype "passive"))
      (node (ref "C118") (pin "1") (pinfunction "1_1") (pintype "passive"))
      (node (ref "C58") (pin "1") (pinfunction "1_1") (pintype "passive"))
      (node (ref "C59") (pin "1") (pinfunction "1_1") (pintype "passive"))
      (node (ref "C60") (pin "1") (pinfunction "1_1") (pintype "passive"))
      (node (ref "C61") (pin "1") (pinfunction "1_1") (pintype "passive"))
      (node (ref "C62") (pin "1") (pinfunction "1_1") (pintype "passive"))
      (node (ref "C63") (pin "1") (pinfunction "1_1") (pintype "passive"))
      (node (ref "C64") (pin "1") (pinfunction "1_1") (pintype "passive"))
      (node (ref "C65") (pin "1") (pinfunction "1_1") (pintype "passive"))
      (node (ref "C66") (pin "1") (pinfunction "1_1") (pintype "passive"))
      (node (ref "C67") (pin "1") (pinfunction "1_1") (pintype "passive"))
      (node (ref "C68") (pin "1") (pinfunction "1_1") (pintype "passive"))
      (node (ref "C69") (pin "1") (pinfunction "1_1") (pintype "passive"))
      (node (ref "C72") (pin "2") (pinfunction "2_2") (pintype "passive"))
      (node (ref "C73") (pin "2") (pinfunction "2_2") (pintype "passive"))
      (node (ref "C74") (pin "1") (pinfunction "1_1") (pintype "power_in"))
      (node (ref "C76") (pin "1") (pinfunction "1_1") (pintype "passive"))
      (node (ref "C77") (pin "1") (pinfunction "1_1") (pintype "passive"))
      (node (ref "C78") (pin "1") (pinfunction "1_1") (pintype "passive"))
      (node (ref "C79") (pin "2") (pinfunction "2_2") (pintype "passive"))
      (node (ref "C80") (pin "1") (pinfunction "1_1") (pintype "passive"))
      (node (ref "C81") (pin "1") (pinfunction "1_1") (pintype "passive"))
      (node (ref "C82") (pin "2") (pinfunction "2_2") (pintype "passive"))
      (node (ref "C83") (pin "1") (pinfunction "1_1") (pintype "passive"))
      (node (ref "C84") (pin "1") (pinfunction "1_1") (pintype "passive"))
      (node (ref "C85") (pin "2") (pinfunction "2_2") (pintype "passive"))
      (node (ref "C86") (pin "1") (pinfunction "1_1") (pintype "passive"))
      (node (ref "C87") (pin "1") (pinfunction "1_1") (pintype "passive"))
      (node (ref "C88") (pin "1") (pinfunction "1_1") (pintype "passive"))
      (node (ref "C89") (pin "2") (pinfunction "2_2") (pintype "passive"))
      (node (ref "C90") (pin "1") (pinfunction "1_1") (pintype "passive"))
      (node (ref "C91") (pin "1") (pinfunction "1_1") (pintype "passive"))
      (node (ref "C92") (pin "1") (pinfunction "1_1") (pintype "passive"))
      (node (ref "C93") (pin "1") (pinfunction "1_1") (pintype "passive"))
      (node (ref "C94") (pin "2") (pinfunction "2_2") (pintype "passive"))
      (node (ref "C95") (pin "1") (pinfunction "1_1") (pintype "passive"))
      (node (ref "C96") (pin "1") (pinfunction "1_1") (pintype "passive"))
      (node (ref "C97") (pin "2") (pinfunction "2_2") (pintype "passive"))
      (node (ref "C98") (pin "1") (pinfunction "1_1") (pintype "passive"))
      (node (ref "C99") (pin "1") (pinfunction "1_1") (pintype "passive"))
      (node (ref "DD1") (pin "177") (pinfunction "VSS_177") (pintype "power_in"))
      (node (ref "DD1") (pin "32") (pinfunction "VrefLOC_32") (pintype "power_in"))
      (node (ref "DD1") (pin "33") (pinfunction "VrefLOA_33") (pintype "power_in"))
      (node (ref "DD1") (pin "34") (pinfunction "VSSA_34") (pintype "power_in"))
      (node (ref "DD1") (pin "50") (pinfunction "VrefLOB_50") (pintype "power_in"))
      (node (ref "DD1") (pin "51") (pinfunction "VrefLOD_51") (pintype "power_in"))
      (node (ref "DD1") (pin "52") (pinfunction "VSSA_52") (pintype "power_in"))
      (node (ref "DD4") (pin "3") (pinfunction "SGND_3") (pintype "passive"))
      (node (ref "DD4") (pin "6") (pinfunction "GND_6") (pintype "passive"))
      (node (ref "DD5") (pin "0") (pinfunction "PAD_0") (pintype "passive"))
      (node (ref "DD5") (pin "2") (pinfunction "GND_2") (pintype "passive"))
      (node (ref "DD5") (pin "3") (pinfunction "MODE_3") (pintype "passive"))
      (node (ref "NT19") (pin "2") (pinfunction "2_2") (pintype "passive"))
      (node (ref "R76") (pin "1") (pinfunction "1_1") (pintype "passive"))
      (node (ref "R78") (pin "1") (pinfunction "1_1") (pintype "passive"))
      (node (ref "X1") (pin "10") (pinfunction "10_10") (pintype "power_in"))
    )
    (net (code "17") (name "Net-(DD1C-VSSOSC)") (class "Default")
      (node (ref "C70") (pin "1") (pinfunction "1_1") (pintype "passive"))
      (node (ref "C71") (pin "1") (pinfunction "1_1") (pintype "passive"))
      (node (ref "DD1") (pin "122") (pinfunction "VSSOSC_122") (pintype "passive"))
      (node (ref "NT19") (pin "1") (pinfunction "1_1") (pintype "passive"))
    )
    (net (code "18") (name "Net-(DD1C-VrefHIA)") (class "Default")
      (node (ref "C62") (pin "2") (pinfunction "2_2") (pintype "passive"))
      (node (ref "C66") (pin "2") (pinfunction "2_2") (pintype "passive"))
      (node (ref "DD1") (pin "35") (pinfunction "VrefHIC_35") (pintype "power_in"))
      (node (ref "DD1") (pin "37") (pinfunction "VrefHIA_37") (pintype "power_in"))
      (node (ref "R73") (pin "1") (pinfunction "1_1") (pintype "passive"))
    )
    (net (code "19") (name "Net-(DD1C-VrefHIB)") (class "Default")
      (node (ref "C63") (pin "2") (pinfunction "2_2") (pintype "passive"))
      (node (ref "C67") (pin "2") (pinfunction "2_2") (pintype "passive"))
      (node (ref "DD1") (pin "53") (pinfunction "VrefHIB_53") (pintype "power_in"))
      (node (ref "DD1") (pin "55") (pinfunction "VrefHID_55") (pintype "power_in"))
      (node (ref "R74") (pin "1") (pinfunction "1_1") (pintype "passive"))
    )
    (net (code "20") (name "Net-(DD1C-X1)") (class "Default")
      (node (ref "C70") (pin "2") (pinfunction "2_2") (pintype "passive"))
      (node (ref "DD1") (pin "123") (pinfunction "X1_123") (pintype "passive"))
      (node (ref "Z1") (pin "1") (pinfunction "1_1") (pintype "passive"))
    )
    (net (code "21") (name "Net-(DD1C-X2)") (class "Default")
      (node (ref "C71") (pin "2") (pinfunction "2_2") (pintype "passive"))
      (node (ref "DD1") (pin "121") (pinfunction "X2_121") (pintype "passive"))
      (node (ref "Z1") (pin "2") (pinfunction "2_2") (pintype "passive"))
    )
    (net (code "22") (name "Net-(DD4-BST)") (class "Default")
      (node (ref "C75") (pin "2") (pinfunction "2_2") (pintype "passive"))
      (node (ref "DD4") (pin "1") (pinfunction "BST_1") (pintype "passive"))
    )
    (net (code "23") (name "Net-(DD4-CTRL)") (class "Default")
      (node (ref "DD4") (pin "5") (pinfunction "CTRL_5") (pintype "passive"))
      (node (ref "R75") (pin "1") (pinfunction "1_1") (pintype "passive"))
      (node (ref "R76") (pin "2") (pinfunction "2_2") (pintype "passive"))
    )
    (net (code "24") (name "Net-(DD4-LX)") (class "Default")
      (node (ref "C75") (pin "1") (pinfunction "1_1") (pintype "passive"))
      (node (ref "DD4") (pin "8") (pinfunction "LX_8") (pintype "passive"))
      (node (ref "L8") (pin "2") (pinfunction "2_2") (pintype "passive"))
    )
    (net (code "25") (name "Net-(DD4-VD)") (class "Default")
      (node (ref "C76") (pin "2") (pinfunction "2_2") (pintype "passive"))
      (node (ref "DD4") (pin "2") (pinfunction "VD_2") (pintype "passive"))
    )
    (net (code "26") (name "Net-(DD5-FB)") (class "Default")
      (node (ref "DD5") (pin "4") (pinfunction "FB_4") (pintype "passive"))
      (node (ref "R78") (pin "2") (pinfunction "2_2") (pintype "passive"))
      (node (ref "R79") (pin "2") (pinfunction "2_2") (pintype "passive"))
    )
    (net (code "27") (name "Net-(DD5-PG)") (class "Default")
      (node (ref "DD5") (pin "6") (pinfunction "PG_6") (pintype "passive"))
      (node (ref "R77") (pin "2") (pinfunction "2_2") (pintype "passive"))
    )
    (net (code "28") (name "Net-(DD5-SW)") (class "Default")
      (node (ref "DD5") (pin "7") (pinfunction "SW_7") (pintype "passive"))
      (node (ref "L9") (pin "2") (pinfunction "2_2") (pintype "passive"))
    )
    (net (code "29") (name "Net-(L3-Pad2)") (class "Default")
      (node (ref "L3") (pin "2") (pinfunction "2_2") (pintype "passive"))
      (node (ref "R74") (pin "2") (pinfunction "2_2") (pintype "passive"))
    )
    (net (code "30") (name "Net-(L4-Pad2)") (class "Default")
      (node (ref "L4") (pin "2") (pinfunction "2_2") (pintype "passive"))
      (node (ref "R73") (pin "2") (pinfunction "2_2") (pintype "passive"))
    )
    (net (code "31") (name "Net-(L7-Pad2)") (class "Default")
      (node (ref "L7") (pin "2") (pinfunction "2_2") (pintype "passive"))
      (node (ref "X1") (pin "1") (pinfunction "1_1") (pintype "passive"))
    )
    (net (code "32") (name "unconnected-(DD1C-ERR_RST-Pad92)") (class "Default")
      (node (ref "DD1") (pin "92") (pinfunction "ERR_RST_92") (pintype "power_in"))
    )
    (net (code "33") (name "unconnected-(DD1C-FLT1-Pad73)") (class "Default")
      (node (ref "DD1") (pin "73") (pinfunction "FLT1_73") (pintype "power_in"))
    )
    (net (code "34") (name "unconnected-(DD1C-FLT2-Pad74)") (class "Default")
      (node (ref "DD1") (pin "74") (pinfunction "FLT2_74") (pintype "power_in"))
    )
  )
)
